# sandh.net
KiCad netlist of a schematic drawn in EAGLE
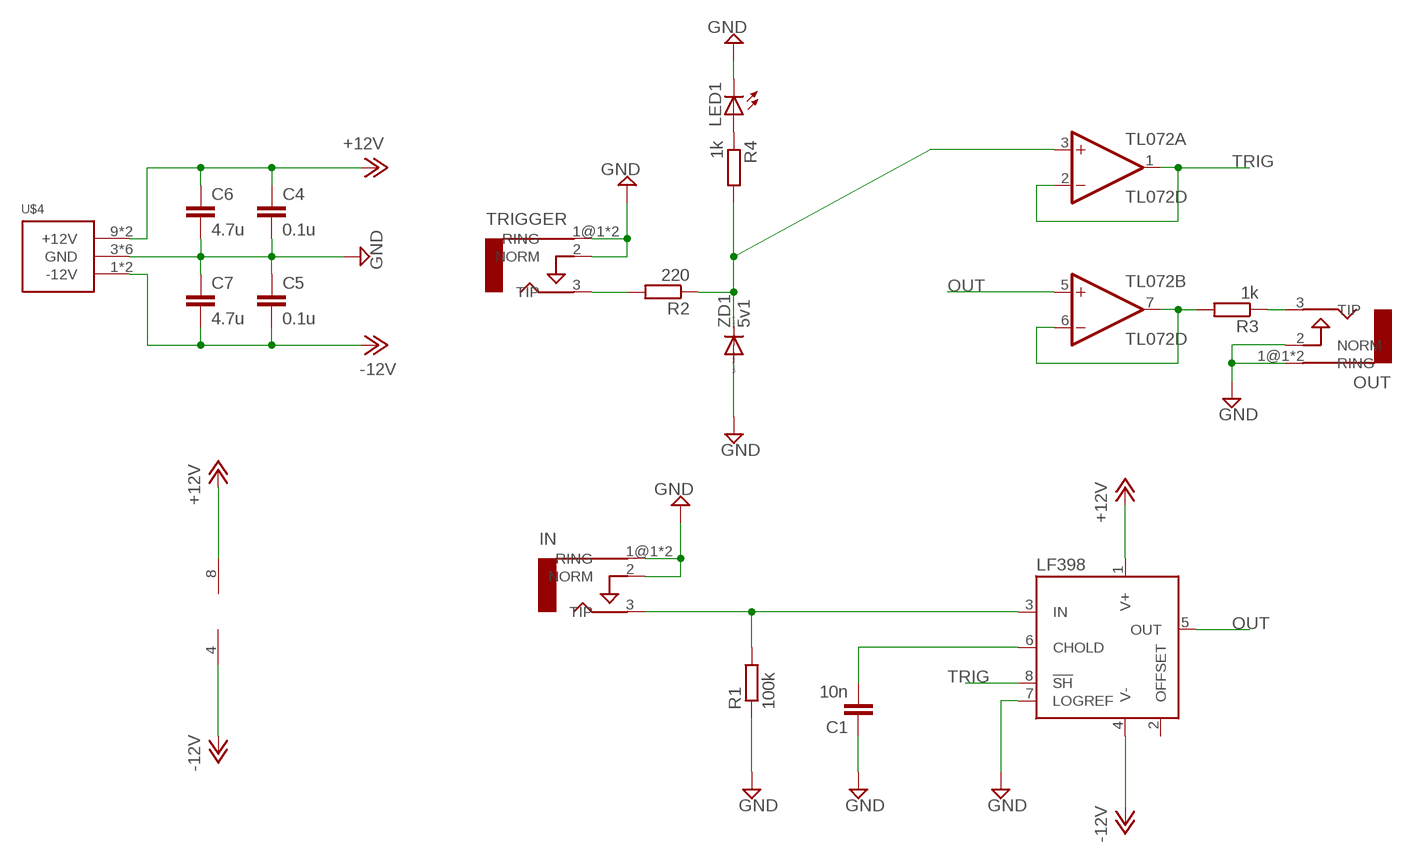
[diagram p0: schematic, sheet 1]

(export (version "E")
  (design (tool "Eeschema 10.0.6"))
  (components
    (comp (ref "C1")
      (value "10n")
      (footprint "eagle-import:C0805")
      (libsource (lib "eagle-import") (part "C-EUC0805"))
    )
    (comp (ref "C4")
      (value "0.1u")
      (footprint "eagle-import:C0805")
      (libsource (lib "eagle-import") (part "C-EUC0805"))
    )
    (comp (ref "C5")
      (value "0.1u")
      (footprint "eagle-import:C0805")
      (libsource (lib "eagle-import") (part "C-EUC0805"))
    )
    (comp (ref "C6")
      (value "4.7u")
      (footprint "eagle-import:C0805")
      (libsource (lib "eagle-import") (part "C-EUC0805"))
    )
    (comp (ref "C7")
      (value "4.7u")
      (footprint "eagle-import:C0805")
      (libsource (lib "eagle-import") (part "C-EUC0805"))
    )
    (comp (ref "IN")
      (value "AUDIO-JACKERTHENVAR")
      (footprint "eagle-import:ERTHENVAR-JACK")
      (libsource (lib "eagle-import") (part "AUDIO-JACKERTHENVAR"))
    )
    (comp (ref "LED1")
      (value "LEDCHIP-LED0805")
      (footprint "eagle-import:CHIP-LED0805")
      (libsource (lib "eagle-import") (part "LEDCHIP-LED0805"))
    )
    (comp (ref "LF398")
      (value "LF398AD")
      (footprint "eagle-import:SO08")
      (libsource (lib "eagle-import") (part "LF398AD"))
    )
    (comp (ref "OUT")
      (value "AUDIO-JACKERTHENVAR")
      (footprint "eagle-import:ERTHENVAR-JACK")
      (libsource (lib "eagle-import") (part "AUDIO-JACKERTHENVAR"))
    )
    (comp (ref "R1")
      (value "100k")
      (footprint "eagle-import:R0805")
      (libsource (lib "eagle-import") (part "R-EU_R0805"))
    )
    (comp (ref "R2")
      (value "220")
      (footprint "eagle-import:R0805")
      (libsource (lib "eagle-import") (part "R-EU_R0805"))
    )
    (comp (ref "R3")
      (value "1k")
      (footprint "eagle-import:R0805")
      (libsource (lib "eagle-import") (part "R-EU_R0805"))
    )
    (comp (ref "R4")
      (value "1k")
      (footprint "eagle-import:R0805")
      (libsource (lib "eagle-import") (part "R-EU_R0805"))
    )
    (comp (ref "TL072")
      (value "TL072D")
      (footprint "eagle-import:SO08")
      (libsource (lib "eagle-import") (part "TL072D"))
    )
    (comp (ref "TRIGGER")
      (value "AUDIO-JACKERTHENVAR")
      (footprint "eagle-import:ERTHENVAR-JACK")
      (libsource (lib "eagle-import") (part "AUDIO-JACKERTHENVAR"))
    )
    (comp (ref "U$4")
      (value "POWER_SIMPLE10")
      (footprint "eagle-import:POWER_10")
      (libsource (lib "eagle-import") (part "POWER_SIMPLE10"))
    )
    (comp (ref "ZD1")
      (value "5v1")
      (footprint "eagle-import:SOD323-W")
      (libsource (lib "eagle-import") (part "DIODE-SOD323-W"))
    )
  )
  (nets
    (net (code "1") (name "+12V") (class "Default")
      (node (ref "C4") (pin "1") (pinfunction "1_1") (pintype "passive"))
      (node (ref "C6") (pin "1") (pinfunction "1_1") (pintype "passive"))
      (node (ref "LF398") (pin "1") (pinfunction "V+_1") (pintype "power_in"))
      (node (ref "TL072") (pin "8") (pinfunction "V+_8") (pintype "power_in"))
      (node (ref "U$4") (pin "10") (pinfunction "+12V_10") (pintype "bidirectional"))
      (node (ref "U$4") (pin "9") (pinfunction "+12V_9") (pintype "bidirectional"))
    )
    (net (code "2") (name "-12V") (class "Default")
      (node (ref "C5") (pin "2") (pinfunction "2_2") (pintype "passive"))
      (node (ref "C7") (pin "2") (pinfunction "2_2") (pintype "passive"))
      (node (ref "LF398") (pin "4") (pinfunction "V-_4") (pintype "power_in"))
      (node (ref "TL072") (pin "4") (pinfunction "V-_4") (pintype "power_in"))
      (node (ref "U$4") (pin "1") (pinfunction "-12V_1") (pintype "bidirectional"))
      (node (ref "U$4") (pin "2") (pinfunction "-12V_2") (pintype "bidirectional"))
    )
    (net (code "3") (name "/OUT") (class "Default")
      (node (ref "LF398") (pin "5") (pinfunction "OUT_5") (pintype "output"))
      (node (ref "TL072") (pin "5") (pinfunction "+IN_5") (pintype "input"))
    )
    (net (code "4") (name "/TRIG") (class "Default")
      (node (ref "LF398") (pin "8") (pinfunction "~{SH}_8") (pintype "input"))
      (node (ref "R2") (pin "1") (pinfunction "1_1") (pintype "passive"))
      (node (ref "R4") (pin "2") (pinfunction "2_2") (pintype "passive"))
      (node (ref "TL072") (pin "1") (pinfunction "OUT_1") (pintype "output"))
      (node (ref "TL072") (pin "2") (pinfunction "-IN_2") (pintype "input"))
      (node (ref "TL072") (pin "3") (pinfunction "+IN_3") (pintype "input"))
      (node (ref "ZD1") (pin "C") (pinfunction "C_C") (pintype "passive"))
    )
    (net (code "5") (name "GND") (class "Default")
      (node (ref "C1") (pin "1") (pinfunction "1_1") (pintype "passive"))
      (node (ref "C4") (pin "2") (pinfunction "2_2") (pintype "passive"))
      (node (ref "C5") (pin "1") (pinfunction "1_1") (pintype "passive"))
      (node (ref "C6") (pin "2") (pinfunction "2_2") (pintype "passive"))
      (node (ref "C7") (pin "1") (pinfunction "1_1") (pintype "passive"))
      (node (ref "IN") (pin "1@1") (pinfunction "RING_1@1") (pintype "bidirectional"))
      (node (ref "IN") (pin "1@2") (pinfunction "RING_1@2") (pintype "bidirectional"))
      (node (ref "IN") (pin "2") (pinfunction "NORM_2") (pintype "bidirectional"))
      (node (ref "LED1") (pin "C") (pinfunction "C_C") (pintype "passive"))
      (node (ref "LF398") (pin "7") (pinfunction "LOGREF_7") (pintype "power_in"))
      (node (ref "OUT") (pin "1@1") (pinfunction "RING_1@1") (pintype "bidirectional"))
      (node (ref "OUT") (pin "1@2") (pinfunction "RING_1@2") (pintype "bidirectional"))
      (node (ref "OUT") (pin "2") (pinfunction "NORM_2") (pintype "bidirectional"))
      (node (ref "R1") (pin "1") (pinfunction "1_1") (pintype "passive"))
      (node (ref "TRIGGER") (pin "1@1") (pinfunction "RING_1@1") (pintype "bidirectional"))
      (node (ref "TRIGGER") (pin "1@2") (pinfunction "RING_1@2") (pintype "bidirectional"))
      (node (ref "TRIGGER") (pin "2") (pinfunction "NORM_2") (pintype "bidirectional"))
      (node (ref "U$4") (pin "3") (pinfunction "GND_3") (pintype "bidirectional"))
      (node (ref "U$4") (pin "4") (pinfunction "GND_4") (pintype "bidirectional"))
      (node (ref "U$4") (pin "5") (pinfunction "GND_5") (pintype "bidirectional"))
      (node (ref "U$4") (pin "6") (pinfunction "GND_6") (pintype "bidirectional"))
      (node (ref "U$4") (pin "7") (pinfunction "GND_7") (pintype "bidirectional"))
      (node (ref "U$4") (pin "8") (pinfunction "GND_8") (pintype "bidirectional"))
      (node (ref "ZD1") (pin "A") (pinfunction "A_A") (pintype "passive"))
    )
    (net (code "6") (name "Net-(IN-TIP)") (class "Default")
      (node (ref "IN") (pin "3") (pinfunction "TIP_3") (pintype "bidirectional"))
      (node (ref "LF398") (pin "3") (pinfunction "IN_3") (pintype "input"))
      (node (ref "R1") (pin "2") (pinfunction "2_2") (pintype "passive"))
    )
    (net (code "7") (name "Net-(LED1-PadA)") (class "Default")
      (node (ref "LED1") (pin "A") (pinfunction "A_A") (pintype "passive"))
      (node (ref "R4") (pin "1") (pinfunction "1_1") (pintype "passive"))
    )
    (net (code "8") (name "Net-(LF398-CHOLD)") (class "Default")
      (node (ref "C1") (pin "2") (pinfunction "2_2") (pintype "passive"))
      (node (ref "LF398") (pin "6") (pinfunction "CHOLD_6") (pintype "passive"))
    )
    (net (code "9") (name "Net-(OUT-TIP)") (class "Default")
      (node (ref "OUT") (pin "3") (pinfunction "TIP_3") (pintype "bidirectional"))
      (node (ref "R3") (pin "1") (pinfunction "1_1") (pintype "passive"))
    )
    (net (code "10") (name "Net-(TL072B--IN)") (class "Default")
      (node (ref "R3") (pin "2") (pinfunction "2_2") (pintype "passive"))
      (node (ref "TL072") (pin "6") (pinfunction "-IN_6") (pintype "input"))
      (node (ref "TL072") (pin "7") (pinfunction "OUT_7") (pintype "output"))
    )
    (net (code "11") (name "Net-(TRIGGER-TIP)") (class "Default")
      (node (ref "R2") (pin "2") (pinfunction "2_2") (pintype "passive"))
      (node (ref "TRIGGER") (pin "3") (pinfunction "TIP_3") (pintype "bidirectional"))
    )
    (net (code "12") (name "unconnected-(LF398-OFFSET-Pad2)") (class "Default")
      (node (ref "LF398") (pin "2") (pinfunction "OFFSET_2") (pintype "input"))
    )
  )
)
